# Interconnect_board_limit_switches_v1p0.net
KiCad netlist of a schematic drawn in EAGLE
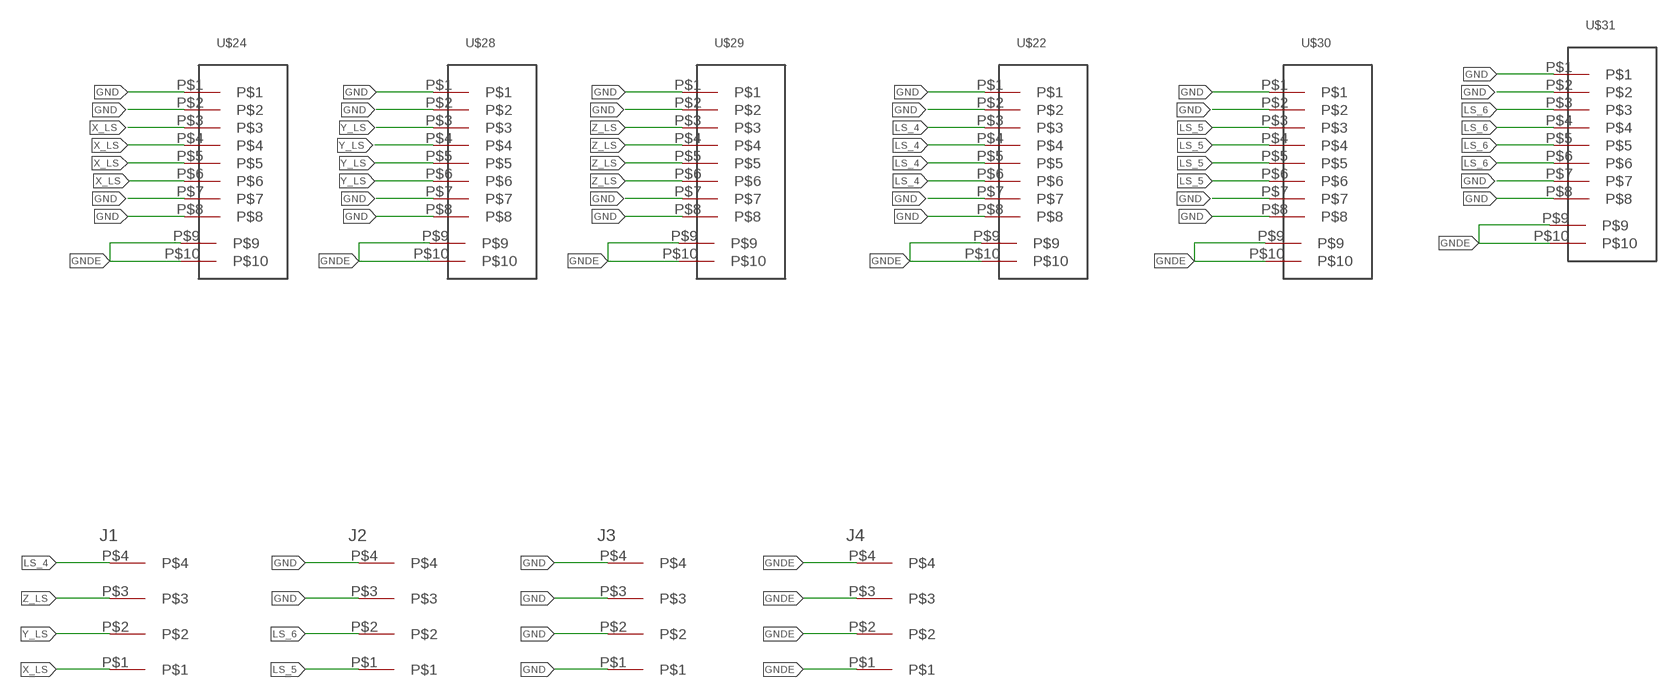
[diagram p0: schematic, sheet 1]

(export (version "E")
  (design (tool "Eeschema 10.0.6"))
  (components
    (comp (ref "J1")
      (value "3.81MM_1_X_4_RT_ANGLE_PLUG_HEADER")
      (footprint "eagle-import:1X4_3.81MM_PITCH")
      (libsource (lib "eagle-import") (part "3.81MM_1_X_4_RT_ANGLE_PLUG_HEADER"))
    )
    (comp (ref "J2")
      (value "3.81MM_1_X_4_RT_ANGLE_PLUG_HEADER")
      (footprint "eagle-import:1X4_3.81MM_PITCH")
      (libsource (lib "eagle-import") (part "3.81MM_1_X_4_RT_ANGLE_PLUG_HEADER"))
    )
    (comp (ref "J3")
      (value "3.81MM_1_X_4_RT_ANGLE_PLUG_HEADER")
      (footprint "eagle-import:1X4_3.81MM_PITCH")
      (libsource (lib "eagle-import") (part "3.81MM_1_X_4_RT_ANGLE_PLUG_HEADER"))
    )
    (comp (ref "J4")
      (value "3.81MM_1_X_4_RT_ANGLE_PLUG_HEADER")
      (footprint "eagle-import:1X4_3.81MM_PITCH")
      (libsource (lib "eagle-import") (part "3.81MM_1_X_4_RT_ANGLE_PLUG_HEADER"))
    )
    (comp (ref "U$22")
      (value "RJ45_SMTRJ")
      (footprint "eagle-import:RJ45_SMT")
      (libsource (lib "eagle-import") (part "RJ45_SMTRJ"))
    )
    (comp (ref "U$24")
      (value "RJ45_SMTRJ")
      (footprint "eagle-import:RJ45_SMT")
      (libsource (lib "eagle-import") (part "RJ45_SMTRJ"))
    )
    (comp (ref "U$28")
      (value "RJ45_SMTRJ")
      (footprint "eagle-import:RJ45_SMT")
      (libsource (lib "eagle-import") (part "RJ45_SMTRJ"))
    )
    (comp (ref "U$29")
      (value "RJ45_SMTRJ")
      (footprint "eagle-import:RJ45_SMT")
      (libsource (lib "eagle-import") (part "RJ45_SMTRJ"))
    )
    (comp (ref "U$30")
      (value "RJ45_SMTRJ")
      (footprint "eagle-import:RJ45_SMT")
      (libsource (lib "eagle-import") (part "RJ45_SMTRJ"))
    )
    (comp (ref "U$31")
      (value "RJ45_SMTRJ")
      (footprint "eagle-import:RJ45_SMT")
      (libsource (lib "eagle-import") (part "RJ45_SMTRJ"))
    )
  )
  (nets
    (net (code "1") (name "GND") (class "Default")
      (node (ref "J2") (pin "P$3") (pinfunction "P$3_P$3") (pintype "bidirectional"))
      (node (ref "J2") (pin "P$4") (pinfunction "P$4_P$4") (pintype "bidirectional"))
      (node (ref "J3") (pin "P$1") (pinfunction "P$1_P$1") (pintype "bidirectional"))
      (node (ref "J3") (pin "P$2") (pinfunction "P$2_P$2") (pintype "bidirectional"))
      (node (ref "J3") (pin "P$3") (pinfunction "P$3_P$3") (pintype "bidirectional"))
      (node (ref "J3") (pin "P$4") (pinfunction "P$4_P$4") (pintype "bidirectional"))
      (node (ref "U$22") (pin "P$1") (pinfunction "P$1_P$1") (pintype "bidirectional"))
      (node (ref "U$22") (pin "P$2") (pinfunction "P$2_P$2") (pintype "bidirectional"))
      (node (ref "U$22") (pin "P$7") (pinfunction "P$7_P$7") (pintype "bidirectional"))
      (node (ref "U$22") (pin "P$8") (pinfunction "P$8_P$8") (pintype "bidirectional"))
      (node (ref "U$24") (pin "P$1") (pinfunction "P$1_P$1") (pintype "bidirectional"))
      (node (ref "U$24") (pin "P$2") (pinfunction "P$2_P$2") (pintype "bidirectional"))
      (node (ref "U$24") (pin "P$7") (pinfunction "P$7_P$7") (pintype "bidirectional"))
      (node (ref "U$24") (pin "P$8") (pinfunction "P$8_P$8") (pintype "bidirectional"))
      (node (ref "U$28") (pin "P$1") (pinfunction "P$1_P$1") (pintype "bidirectional"))
      (node (ref "U$28") (pin "P$2") (pinfunction "P$2_P$2") (pintype "bidirectional"))
      (node (ref "U$28") (pin "P$7") (pinfunction "P$7_P$7") (pintype "bidirectional"))
      (node (ref "U$28") (pin "P$8") (pinfunction "P$8_P$8") (pintype "bidirectional"))
      (node (ref "U$29") (pin "P$1") (pinfunction "P$1_P$1") (pintype "bidirectional"))
      (node (ref "U$29") (pin "P$2") (pinfunction "P$2_P$2") (pintype "bidirectional"))
      (node (ref "U$29") (pin "P$7") (pinfunction "P$7_P$7") (pintype "bidirectional"))
      (node (ref "U$29") (pin "P$8") (pinfunction "P$8_P$8") (pintype "bidirectional"))
      (node (ref "U$30") (pin "P$1") (pinfunction "P$1_P$1") (pintype "bidirectional"))
      (node (ref "U$30") (pin "P$2") (pinfunction "P$2_P$2") (pintype "bidirectional"))
      (node (ref "U$30") (pin "P$7") (pinfunction "P$7_P$7") (pintype "bidirectional"))
      (node (ref "U$30") (pin "P$8") (pinfunction "P$8_P$8") (pintype "bidirectional"))
      (node (ref "U$31") (pin "P$1") (pinfunction "P$1_P$1") (pintype "bidirectional"))
      (node (ref "U$31") (pin "P$2") (pinfunction "P$2_P$2") (pintype "bidirectional"))
      (node (ref "U$31") (pin "P$7") (pinfunction "P$7_P$7") (pintype "bidirectional"))
      (node (ref "U$31") (pin "P$8") (pinfunction "P$8_P$8") (pintype "bidirectional"))
    )
    (net (code "2") (name "GNDE") (class "Default")
      (node (ref "J4") (pin "P$1") (pinfunction "P$1_P$1") (pintype "bidirectional"))
      (node (ref "J4") (pin "P$2") (pinfunction "P$2_P$2") (pintype "bidirectional"))
      (node (ref "J4") (pin "P$3") (pinfunction "P$3_P$3") (pintype "bidirectional"))
      (node (ref "J4") (pin "P$4") (pinfunction "P$4_P$4") (pintype "bidirectional"))
      (node (ref "U$22") (pin "P$10") (pinfunction "P$10_P$10") (pintype "bidirectional"))
      (node (ref "U$22") (pin "P$9") (pinfunction "P$9_P$9") (pintype "bidirectional"))
      (node (ref "U$24") (pin "P$10") (pinfunction "P$10_P$10") (pintype "bidirectional"))
      (node (ref "U$24") (pin "P$9") (pinfunction "P$9_P$9") (pintype "bidirectional"))
      (node (ref "U$28") (pin "P$10") (pinfunction "P$10_P$10") (pintype "bidirectional"))
      (node (ref "U$28") (pin "P$9") (pinfunction "P$9_P$9") (pintype "bidirectional"))
      (node (ref "U$29") (pin "P$10") (pinfunction "P$10_P$10") (pintype "bidirectional"))
      (node (ref "U$29") (pin "P$9") (pinfunction "P$9_P$9") (pintype "bidirectional"))
      (node (ref "U$30") (pin "P$10") (pinfunction "P$10_P$10") (pintype "bidirectional"))
      (node (ref "U$30") (pin "P$9") (pinfunction "P$9_P$9") (pintype "bidirectional"))
      (node (ref "U$31") (pin "P$10") (pinfunction "P$10_P$10") (pintype "bidirectional"))
      (node (ref "U$31") (pin "P$9") (pinfunction "P$9_P$9") (pintype "bidirectional"))
    )
    (net (code "3") (name "LS_4") (class "Default")
      (node (ref "J1") (pin "P$4") (pinfunction "P$4_P$4") (pintype "bidirectional"))
      (node (ref "U$22") (pin "P$3") (pinfunction "P$3_P$3") (pintype "bidirectional"))
      (node (ref "U$22") (pin "P$4") (pinfunction "P$4_P$4") (pintype "bidirectional"))
      (node (ref "U$22") (pin "P$5") (pinfunction "P$5_P$5") (pintype "bidirectional"))
      (node (ref "U$22") (pin "P$6") (pinfunction "P$6_P$6") (pintype "bidirectional"))
    )
    (net (code "4") (name "LS_5") (class "Default")
      (node (ref "J2") (pin "P$1") (pinfunction "P$1_P$1") (pintype "bidirectional"))
      (node (ref "U$30") (pin "P$3") (pinfunction "P$3_P$3") (pintype "bidirectional"))
      (node (ref "U$30") (pin "P$4") (pinfunction "P$4_P$4") (pintype "bidirectional"))
      (node (ref "U$30") (pin "P$5") (pinfunction "P$5_P$5") (pintype "bidirectional"))
      (node (ref "U$30") (pin "P$6") (pinfunction "P$6_P$6") (pintype "bidirectional"))
    )
    (net (code "5") (name "LS_6") (class "Default")
      (node (ref "J2") (pin "P$2") (pinfunction "P$2_P$2") (pintype "bidirectional"))
      (node (ref "U$31") (pin "P$3") (pinfunction "P$3_P$3") (pintype "bidirectional"))
      (node (ref "U$31") (pin "P$4") (pinfunction "P$4_P$4") (pintype "bidirectional"))
      (node (ref "U$31") (pin "P$5") (pinfunction "P$5_P$5") (pintype "bidirectional"))
      (node (ref "U$31") (pin "P$6") (pinfunction "P$6_P$6") (pintype "bidirectional"))
    )
    (net (code "6") (name "X_LS") (class "Default")
      (node (ref "J1") (pin "P$1") (pinfunction "P$1_P$1") (pintype "bidirectional"))
      (node (ref "U$24") (pin "P$3") (pinfunction "P$3_P$3") (pintype "bidirectional"))
      (node (ref "U$24") (pin "P$4") (pinfunction "P$4_P$4") (pintype "bidirectional"))
      (node (ref "U$24") (pin "P$5") (pinfunction "P$5_P$5") (pintype "bidirectional"))
      (node (ref "U$24") (pin "P$6") (pinfunction "P$6_P$6") (pintype "bidirectional"))
    )
    (net (code "7") (name "Y_LS") (class "Default")
      (node (ref "J1") (pin "P$2") (pinfunction "P$2_P$2") (pintype "bidirectional"))
      (node (ref "U$28") (pin "P$3") (pinfunction "P$3_P$3") (pintype "bidirectional"))
      (node (ref "U$28") (pin "P$4") (pinfunction "P$4_P$4") (pintype "bidirectional"))
      (node (ref "U$28") (pin "P$5") (pinfunction "P$5_P$5") (pintype "bidirectional"))
      (node (ref "U$28") (pin "P$6") (pinfunction "P$6_P$6") (pintype "bidirectional"))
    )
    (net (code "8") (name "Z_LS") (class "Default")
      (node (ref "J1") (pin "P$3") (pinfunction "P$3_P$3") (pintype "bidirectional"))
      (node (ref "U$29") (pin "P$3") (pinfunction "P$3_P$3") (pintype "bidirectional"))
      (node (ref "U$29") (pin "P$4") (pinfunction "P$4_P$4") (pintype "bidirectional"))
      (node (ref "U$29") (pin "P$5") (pinfunction "P$5_P$5") (pintype "bidirectional"))
      (node (ref "U$29") (pin "P$6") (pinfunction "P$6_P$6") (pintype "bidirectional"))
    )
  )
)
